# ver1_0.net
KiCad netlist of a schematic drawn in EAGLE
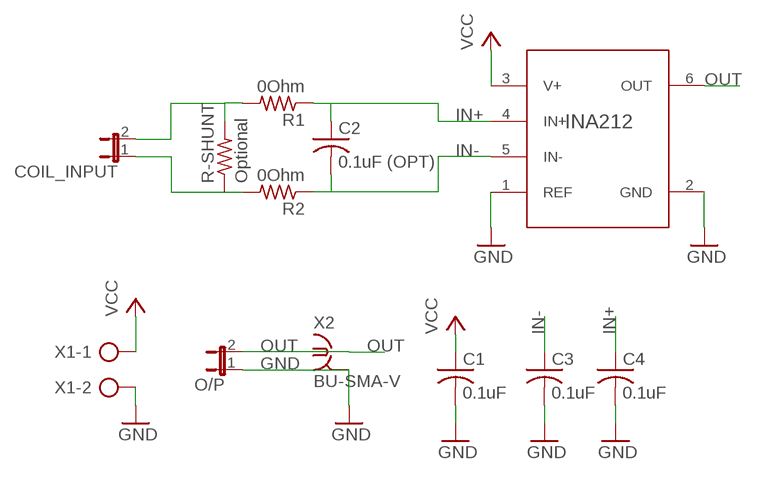
[diagram p0: schematic, sheet 1]

(export (version "E")
  (design (tool "Eeschema 10.0.6"))
  (components
    (comp (ref "C1")
      (value "0.1uF")
      (footprint "eagle-import:C0603")
      (libsource (lib "eagle-import") (part "C-USC0603"))
    )
    (comp (ref "C2")
      (value "0.1uF (OPT)")
      (footprint "eagle-import:C0603")
      (libsource (lib "eagle-import") (part "C-USC0603"))
    )
    (comp (ref "C3")
      (value "0.1uF")
      (footprint "eagle-import:C0603")
      (libsource (lib "eagle-import") (part "C-USC0603"))
    )
    (comp (ref "C4")
      (value "0.1uF")
      (footprint "eagle-import:C0603")
      (libsource (lib "eagle-import") (part "C-USC0603"))
    )
    (comp (ref "COIL_INPUT")
      (value "JP1E")
      (footprint "eagle-import:JP1")
      (libsource (lib "eagle-import") (part "JP1E"))
    )
    (comp (ref "INA212")
      (value "INA212AIDCKR")
      (footprint "eagle-import:DCK0006A_M")
      (libsource (lib "eagle-import") (part "INA212AIDCKR"))
    )
    (comp (ref "O/P")
      (value "JP1E")
      (footprint "eagle-import:JP1")
      (libsource (lib "eagle-import") (part "JP1E"))
    )
    (comp (ref "R-SHUNT")
      (value "Optional")
      (footprint "eagle-import:R0603")
      (libsource (lib "eagle-import") (part "R-US_R0603"))
    )
    (comp (ref "R1")
      (value "0Ohm")
      (footprint "eagle-import:R0603")
      (libsource (lib "eagle-import") (part "R-US_R0603"))
    )
    (comp (ref "R2")
      (value "0Ohm")
      (footprint "eagle-import:R0603")
      (libsource (lib "eagle-import") (part "R-US_R0603"))
    )
    (comp (ref "X1")
      (value "AK500/2")
      (footprint "eagle-import:AK500_2")
      (libsource (lib "eagle-import") (part "AK500/2"))
    )
    (comp (ref "X2")
      (value "BU-SMA-V")
      (footprint "eagle-import:BU-SMA-V")
      (libsource (lib "eagle-import") (part "BU-SMA-V"))
    )
  )
  (nets
    (net (code "1") (name "/IN+") (class "Default")
      (node (ref "C2") (pin "1") (pinfunction "1_1") (pintype "passive"))
      (node (ref "C4") (pin "1") (pinfunction "1_1") (pintype "passive"))
      (node (ref "INA212") (pin "4") (pinfunction "IN+_4") (pintype "input"))
      (node (ref "R1") (pin "1") (pinfunction "1_1") (pintype "passive"))
    )
    (net (code "2") (name "/IN-") (class "Default")
      (node (ref "C2") (pin "2") (pinfunction "2_2") (pintype "passive"))
      (node (ref "C3") (pin "1") (pinfunction "1_1") (pintype "passive"))
      (node (ref "INA212") (pin "5") (pinfunction "IN-_5") (pintype "input"))
      (node (ref "R2") (pin "1") (pinfunction "1_1") (pintype "passive"))
    )
    (net (code "3") (name "/OUT") (class "Default")
      (node (ref "INA212") (pin "6") (pinfunction "OUT_6") (pintype "output"))
      (node (ref "O/P") (pin "2") (pinfunction "2_2") (pintype "passive"))
      (node (ref "X2") (pin "1") (pinfunction "1_1") (pintype "passive"))
    )
    (net (code "4") (name "GND") (class "Default")
      (node (ref "C1") (pin "2") (pinfunction "2_2") (pintype "passive"))
      (node (ref "C3") (pin "2") (pinfunction "2_2") (pintype "passive"))
      (node (ref "C4") (pin "2") (pinfunction "2_2") (pintype "passive"))
      (node (ref "INA212") (pin "1") (pinfunction "REF_1") (pintype "input"))
      (node (ref "INA212") (pin "2") (pinfunction "GND_2") (pintype "power_in"))
      (node (ref "O/P") (pin "1") (pinfunction "1_1") (pintype "passive"))
      (node (ref "X1") (pin "2") (pinfunction "KL_2") (pintype "passive"))
      (node (ref "X2") (pin "2") (pinfunction "2_2") (pintype "passive"))
      (node (ref "X2") (pin "3") (pinfunction "2_3") (pintype "passive"))
      (node (ref "X2") (pin "4") (pinfunction "2_4") (pintype "passive"))
      (node (ref "X2") (pin "5") (pinfunction "2_5") (pintype "passive"))
    )
    (net (code "5") (name "Net-(COIL_INPUT-Pad1)") (class "Default")
      (node (ref "COIL_INPUT") (pin "1") (pinfunction "1_1") (pintype "passive"))
      (node (ref "R-SHUNT") (pin "1") (pinfunction "1_1") (pintype "passive"))
      (node (ref "R2") (pin "2") (pinfunction "2_2") (pintype "passive"))
    )
    (net (code "6") (name "Net-(COIL_INPUT-Pad2)") (class "Default")
      (node (ref "COIL_INPUT") (pin "2") (pinfunction "2_2") (pintype "passive"))
      (node (ref "R-SHUNT") (pin "2") (pinfunction "2_2") (pintype "passive"))
      (node (ref "R1") (pin "2") (pinfunction "2_2") (pintype "passive"))
    )
    (net (code "7") (name "VCC") (class "Default")
      (node (ref "C1") (pin "1") (pinfunction "1_1") (pintype "passive"))
      (node (ref "INA212") (pin "3") (pinfunction "V+_3") (pintype "power_in"))
      (node (ref "X1") (pin "1") (pinfunction "KL_1") (pintype "passive"))
    )
  )
)
